# Zasilanie.net
KiCad netlist of a schematic drawn in Altium Designer
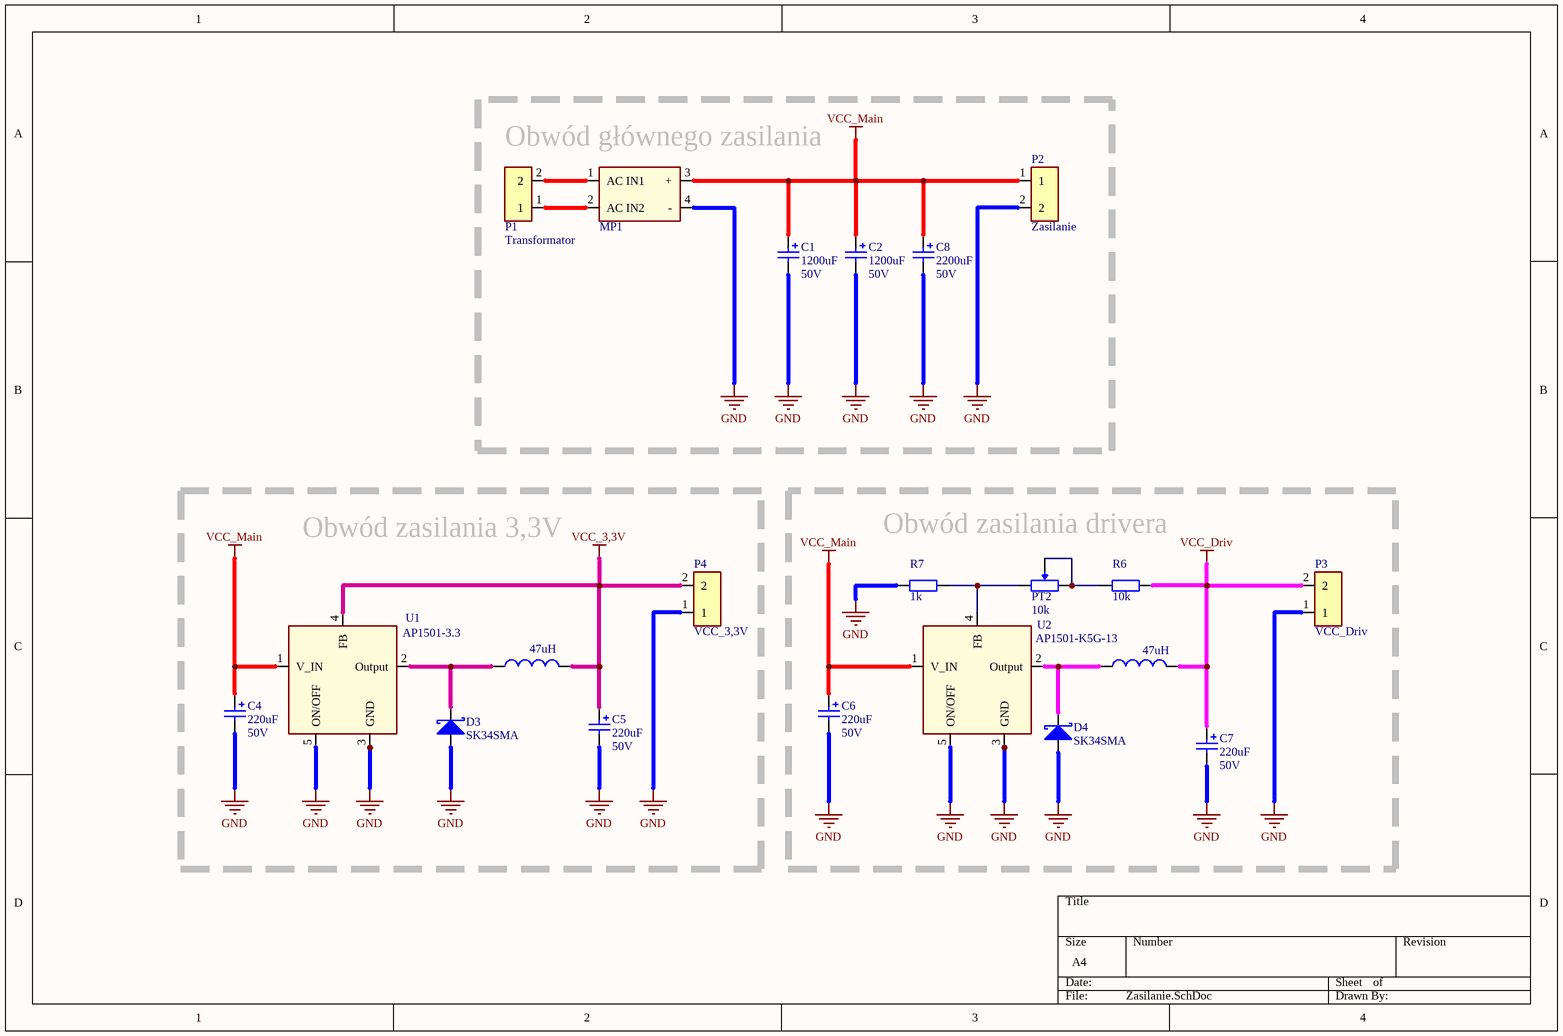
[diagram p0: Zasilanie.SchDoc]

(export (version "E")
  (design (tool "Eeschema 10.0.6"))
  (components
    (comp (ref "C1")
      (value "Kondesator elektrolityczny")
      (footprint "C_POL_D16x25")
      (fields (field (name "PARAMETR_1") "1200uF") (field (name "PARAMETR_2") "50V"))
      (libsource (lib "MyLibrary") (part "Kondesator elektrolityczny"))
    )
    (comp (ref "C2")
      (value "Kondesator elektrolityczny")
      (footprint "C_POL_D16x25")
      (fields (field (name "PARAMETR_1") "1200uF") (field (name "PARAMETR_2") "50V"))
      (libsource (lib "MyLibrary") (part "Kondesator elektrolityczny"))
    )
    (comp (ref "C4")
      (value "Kondesator elektrolityczny")
      (footprint "C_POL_D10x16")
      (fields (field (name "PARAMETR_1") "220uF") (field (name "PARAMETR_2") "50V"))
      (libsource (lib "MyLibrary") (part "Kondesator elektrolityczny"))
    )
    (comp (ref "C5")
      (value "Kondesator elektrolityczny")
      (footprint "C_POL_D10x16")
      (fields (field (name "PARAMETR_1") "220uF") (field (name "PARAMETR_2") "50V"))
      (libsource (lib "MyLibrary") (part "Kondesator elektrolityczny"))
    )
    (comp (ref "C6")
      (value "Kondesator elektrolityczny")
      (footprint "C_POL_D10x16")
      (fields (field (name "PARAMETR_1") "220uF") (field (name "PARAMETR_2") "50V"))
      (libsource (lib "MyLibrary") (part "Kondesator elektrolityczny"))
    )
    (comp (ref "C7")
      (value "Kondesator elektrolityczny")
      (footprint "C_POL_D10x16")
      (fields (field (name "PARAMETR_1") "220uF") (field (name "PARAMETR_2") "50V"))
      (libsource (lib "MyLibrary") (part "Kondesator elektrolityczny"))
    )
    (comp (ref "C8")
      (value "Kondesator elektrolityczny")
      (footprint "MyLibrary:C_POL-D25X50")
      (fields (field (name "PARAMETR_1") "2200uF") (field (name "PARAMETR_2") "50V"))
      (libsource (lib "MyLibrary") (part "Kondesator elektrolityczny"))
    )
    (comp (ref "D3")
      (value "SK34SMA")
      (footprint "DO-214AC")
      (description "Dioda Schottky")
      (fields (field (name "OZNACZENIE") "SK34SMA"))
      (libsource (lib "MyLibrary") (part "SK34SMA"))
    )
    (comp (ref "D4")
      (value "SK34SMA")
      (footprint "DO-214AC")
      (description "Dioda Schottky")
      (fields (field (name "OZNACZENIE") "SK34SMA"))
      (libsource (lib "MyLibrary") (part "SK34SMA"))
    )
    (comp (ref "L2")
      (value "~")
      (footprint "DE1207")
      (description "Cewka")
      (fields (field (name "PARAMETR_1") "47uH"))
      (libsource (lib "MyLibrary") (part "Cewka"))
    )
    (comp (ref "L3")
      (value "~")
      (footprint "DE1207")
      (description "Cewka")
      (fields (field (name "PARAMETR_1") "47uH"))
      (libsource (lib "MyLibrary") (part "Cewka"))
    )
    (comp (ref "MP1")
      (value "KBPC5010W")
      (footprint "KBPC5010W")
      (description "Mostek porstowniczy")
      (libsource (lib "MyLibrary") (part "KBPC5010W"))
    )
    (comp (ref "P1")
      (value "TRAFO")
      (footprint "ARK2-5mm")
      (fields (field (name "OZNACZENIE") "Transformator"))
      (libsource (lib "") (part "Złacze śrubowe_1"))
    )
    (comp (ref "P2")
      (value "VCC_MAIN")
      (footprint "ARK2-5mm")
      (fields (field (name "OZNACZENIE") "Zasilanie"))
      (libsource (lib "") (part "Złacze śrubowe_2"))
    )
    (comp (ref "P3")
      (value "VCC_DRIV")
      (footprint "ARK2-5mm")
      (fields (field (name "OZNACZENIE") "VCC_Driv"))
      (libsource (lib "MyLibrary") (part "Złacze śrubowe"))
    )
    (comp (ref "P4")
      (value "VCC_3,3V")
      (footprint "ARK2-5mm")
      (fields (field (name "OZNACZENIE") "VCC_3,3V"))
      (libsource (lib "MyLibrary") (part "Złacze śrubowe"))
    )
    (comp (ref "PT2")
      (value "Potentiometer")
      (footprint "Potecjomert")
      (description "Potentiometer montażowy wielobortowy")
      (fields (field (name "PARAMETR_1") "10k"))
      (libsource (lib "MyLibrary") (part "Potentiometer"))
    )
    (comp (ref "R6")
      (value "Rezystor")
      (footprint "SMD-1206-RES")
      (fields (field (name "PARAMETR_1") "10k"))
      (libsource (lib "MyLibrary") (part "Rezystor"))
    )
    (comp (ref "R7")
      (value "Rezystor")
      (footprint "SMD-1206-RES")
      (fields (field (name "PARAMETR_1") "1k"))
      (libsource (lib "MyLibrary") (part "Rezystor"))
    )
    (comp (ref "U1")
      (value "AP1501")
      (footprint "TO263-5L")
      (description "przetwornica DC/DC buck")
      (fields (field (name "OZNACZENIE") "AP1501-3.3"))
      (libsource (lib "MyLibrary") (part "AP1501"))
    )
    (comp (ref "U2")
      (value "AP1501")
      (footprint "TO263-5L")
      (description "przetwornica DC/DC buck")
      (fields (field (name "OZNACZENIE") "AP1501-K5G-13"))
      (libsource (lib "MyLibrary") (part "AP1501"))
    )
  )
  (nets
    (net (code "1") (name "GND") (class "Default")
      (node (ref "C1") (pin "1") (pinfunction "1_1") (pintype "passive"))
      (node (ref "C2") (pin "1") (pinfunction "1_1") (pintype "passive"))
      (node (ref "C4") (pin "1") (pinfunction "1_1") (pintype "passive"))
      (node (ref "C5") (pin "1") (pinfunction "1_1") (pintype "passive"))
      (node (ref "C6") (pin "1") (pinfunction "1_1") (pintype "passive"))
      (node (ref "C7") (pin "1") (pinfunction "1_1") (pintype "passive"))
      (node (ref "C8") (pin "1") (pinfunction "1_1") (pintype "passive"))
      (node (ref "D3") (pin "2") (pinfunction "A_2") (pintype "passive"))
      (node (ref "D4") (pin "2") (pinfunction "A_2") (pintype "passive"))
      (node (ref "MP1") (pin "4") (pinfunction "-_4") (pintype "passive"))
      (node (ref "P2") (pin "2") (pinfunction "2_2") (pintype "passive"))
      (node (ref "P3") (pin "1") (pinfunction "1_1") (pintype "passive"))
      (node (ref "P4") (pin "1") (pinfunction "1_1") (pintype "passive"))
      (node (ref "R7") (pin "2") (pinfunction "2_2") (pintype "passive"))
      (node (ref "U1") (pin "3") (pinfunction "GND_3") (pintype "power_in"))
      (node (ref "U1") (pin "5") (pinfunction "ON/OFF_5") (pintype "passive"))
      (node (ref "U1") (pin "6") (pinfunction "6_6") (pintype "passive"))
      (node (ref "U2") (pin "3") (pinfunction "GND_3") (pintype "power_in"))
      (node (ref "U2") (pin "5") (pinfunction "ON/OFF_5") (pintype "passive"))
      (node (ref "U2") (pin "6") (pinfunction "6_6") (pintype "passive"))
    )
    (net (code "2") (name "Net-(D3-K)") (class "Default")
      (node (ref "D3") (pin "1") (pinfunction "K_1") (pintype "passive"))
      (node (ref "L2") (pin "1") (pinfunction "3_1") (pintype "passive"))
      (node (ref "U1") (pin "2") (pinfunction "Output_2") (pintype "power_in"))
    )
    (net (code "3") (name "Net-(D4-K)") (class "Default")
      (node (ref "D4") (pin "1") (pinfunction "K_1") (pintype "passive"))
      (node (ref "L3") (pin "1") (pinfunction "3_1") (pintype "passive"))
      (node (ref "U2") (pin "2") (pinfunction "Output_2") (pintype "power_in"))
    )
    (net (code "4") (name "Net-(MP1-AC_IN1)") (class "Default")
      (node (ref "MP1") (pin "1") (pinfunction "AC_IN1_1") (pintype "passive"))
      (node (ref "P1") (pin "2") (pinfunction "2_2") (pintype "passive"))
    )
    (net (code "5") (name "Net-(MP1-AC_IN2)") (class "Default")
      (node (ref "MP1") (pin "2") (pinfunction "AC_IN2_2") (pintype "passive"))
      (node (ref "P1") (pin "1") (pinfunction "1_1") (pintype "passive"))
    )
    (net (code "6") (name "Net-(PT2-BOT)") (class "Default")
      (node (ref "PT2") (pin "3") (pinfunction "BOT_3") (pintype "passive"))
      (node (ref "R7") (pin "1") (pinfunction "1_1") (pintype "passive"))
      (node (ref "U2") (pin "4") (pinfunction "FB_4") (pintype "passive"))
    )
    (net (code "7") (name "Net-(PT2-TAP)") (class "Default")
      (node (ref "PT2") (pin "1") (pinfunction "TOP_1") (pintype "passive"))
      (node (ref "PT2") (pin "2") (pinfunction "TAP_2") (pintype "passive"))
      (node (ref "R6") (pin "2") (pinfunction "2_2") (pintype "passive"))
    )
    (net (code "8") (name "VCC_3,3V") (class "Default")
      (node (ref "C5") (pin "2") (pinfunction "2_2") (pintype "passive"))
      (node (ref "L2") (pin "2") (pinfunction "8_2") (pintype "passive"))
      (node (ref "P4") (pin "2") (pinfunction "2_2") (pintype "passive"))
      (node (ref "U1") (pin "4") (pinfunction "FB_4") (pintype "passive"))
    )
    (net (code "9") (name "VCC_Driv") (class "Default")
      (node (ref "C7") (pin "2") (pinfunction "2_2") (pintype "passive"))
      (node (ref "L3") (pin "2") (pinfunction "8_2") (pintype "passive"))
      (node (ref "P3") (pin "2") (pinfunction "2_2") (pintype "passive"))
      (node (ref "R6") (pin "1") (pinfunction "1_1") (pintype "passive"))
    )
    (net (code "10") (name "VCC_Main") (class "Default")
      (node (ref "C1") (pin "2") (pinfunction "2_2") (pintype "passive"))
      (node (ref "C2") (pin "2") (pinfunction "2_2") (pintype "passive"))
      (node (ref "C4") (pin "2") (pinfunction "2_2") (pintype "passive"))
      (node (ref "C6") (pin "2") (pinfunction "2_2") (pintype "passive"))
      (node (ref "C8") (pin "2") (pinfunction "2_2") (pintype "passive"))
      (node (ref "MP1") (pin "3") (pinfunction "+_3") (pintype "passive"))
      (node (ref "P2") (pin "1") (pinfunction "1_1") (pintype "passive"))
      (node (ref "U1") (pin "1") (pinfunction "V_IN_1") (pintype "power_in"))
      (node (ref "U2") (pin "1") (pinfunction "V_IN_1") (pintype "power_in"))
    )
  )
)
